# Pulse_Oximeter_Board.net
KiCad netlist of a schematic drawn in EAGLE
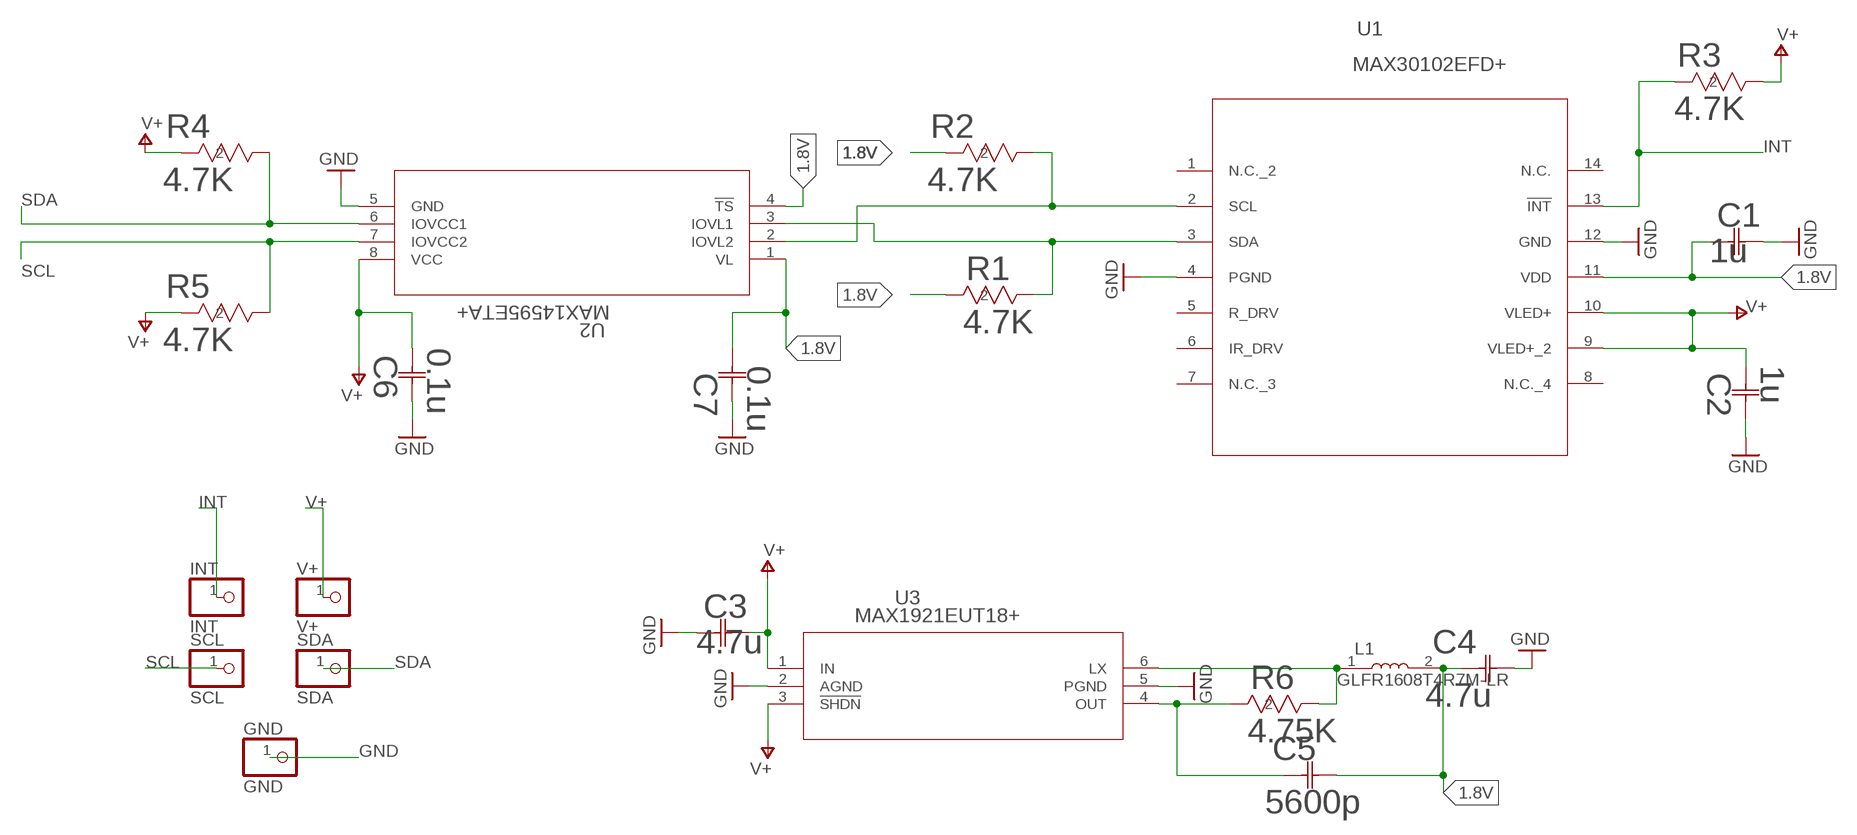
[diagram p0: schematic, sheet 1]

(export (version "E")
  (design (tool "Eeschema 10.0.6"))
  (components
    (comp (ref "C1")
      (value "1u")
      (footprint "eagle-import:CAP_CHIP2_1X0P5")
      (fields (field (name "MANUFACTURER_PART_NUMBER") "GRM155R61A105KE15D"))
      (libsource (lib "eagle-import") (part "GRM155R61A105KE15D"))
    )
    (comp (ref "C2")
      (value "1u")
      (footprint "eagle-import:CAP_CHIP2_1X0P5")
      (fields (field (name "MANUFACTURER_PART_NUMBER") "GRM155R61A105KE15D"))
      (libsource (lib "eagle-import") (part "GRM155R61A105KE15D"))
    )
    (comp (ref "C3")
      (value "4.7u")
      (footprint "eagle-import:CAP_CHIP2_1X0P5")
      (fields (field (name "MANUFACTURER_PART_NUMBER") "GRM155R61A105KE15D"))
      (libsource (lib "eagle-import") (part "GRM155R61A105KE15D"))
    )
    (comp (ref "C4")
      (value "4.7u")
      (footprint "eagle-import:CAP_CHIP2_1X0P5")
      (fields (field (name "MANUFACTURER_PART_NUMBER") "GRM155R61A105KE15D"))
      (libsource (lib "eagle-import") (part "GRM155R61A105KE15D"))
    )
    (comp (ref "C5")
      (value "5600p")
      (footprint "eagle-import:CAP_CHIP2_1X0P5")
      (fields (field (name "MANUFACTURER_PART_NUMBER") "GRM155R61A105KE15D"))
      (libsource (lib "eagle-import") (part "GRM155R61A105KE15D"))
    )
    (comp (ref "C6")
      (value "0.1u")
      (footprint "eagle-import:CAP_CHIP2_1X0P5")
      (fields (field (name "MANUFACTURER_PART_NUMBER") "GRM155R61A105KE15D"))
      (libsource (lib "eagle-import") (part "GRM155R61A105KE15D"))
    )
    (comp (ref "C7")
      (value "0.1u")
      (footprint "eagle-import:CAP_CHIP2_1X0P5")
      (fields (field (name "MANUFACTURER_PART_NUMBER") "GRM155R61A105KE15D"))
      (libsource (lib "eagle-import") (part "GRM155R61A105KE15D"))
    )
    (comp (ref "GND")
      (value "GND")
      (footprint "eagle-import:1X01")
      (libsource (lib "eagle-import") (part "PINHD-1X1"))
    )
    (comp (ref "INT")
      (value "INT")
      (footprint "eagle-import:1X01")
      (libsource (lib "eagle-import") (part "PINHD-1X1"))
    )
    (comp (ref "L1")
      (value "GLFR1608T4R7M-LR")
      (footprint "eagle-import:INDC1608X95N")
      (fields (field (name "DIGI-KEY_PART_NUMBER") "445-3607-1-ND") (field (name "MF") "TDK"))
      (libsource (lib "eagle-import") (part "GLFR1608T4R7M-LR"))
    )
    (comp (ref "R1")
      (value "4.7K")
      (footprint "eagle-import:RES0402_CRG_TYCO")
      (fields (field (name "MANUFACTURER_PART_NUMBER") "CRG0402J1K010"))
      (libsource (lib "eagle-import") (part "CRG0402J1K0/10"))
    )
    (comp (ref "R2")
      (value "4.7K")
      (footprint "eagle-import:RES0402_CRG_TYCO")
      (fields (field (name "MANUFACTURER_PART_NUMBER") "CRG0402J1K010"))
      (libsource (lib "eagle-import") (part "CRG0402J1K0/10"))
    )
    (comp (ref "R3")
      (value "4.7K")
      (footprint "eagle-import:RES0402_CRG_TYCO")
      (fields (field (name "MANUFACTURER_PART_NUMBER") "CRG0402J1K010"))
      (libsource (lib "eagle-import") (part "CRG0402J1K0/10"))
    )
    (comp (ref "R4")
      (value "4.7K")
      (footprint "eagle-import:RES0402_CRG_TYCO")
      (fields (field (name "MANUFACTURER_PART_NUMBER") "CRG0402J1K010"))
      (libsource (lib "eagle-import") (part "CRG0402J1K0/10"))
    )
    (comp (ref "R5")
      (value "4.7K")
      (footprint "eagle-import:RES0402_CRG_TYCO")
      (fields (field (name "MANUFACTURER_PART_NUMBER") "CRG0402J1K010"))
      (libsource (lib "eagle-import") (part "CRG0402J1K0/10"))
    )
    (comp (ref "R6")
      (value "4.75K")
      (footprint "eagle-import:RES0402_CRG_TYCO")
      (fields (field (name "MANUFACTURER_PART_NUMBER") "CRG0402J1K010"))
      (libsource (lib "eagle-import") (part "CRG0402J1K0/10"))
    )
    (comp (ref "SCL")
      (value "SCL")
      (footprint "eagle-import:1X01")
      (libsource (lib "eagle-import") (part "PINHD-1X1"))
    )
    (comp (ref "SDA")
      (value "SDA")
      (footprint "eagle-import:1X01")
      (libsource (lib "eagle-import") (part "PINHD-1X1"))
    )
    (comp (ref "U1")
      (value "MAX30102EFD+")
      (footprint "eagle-import:21-0880B")
      (libsource (lib "eagle-import") (part "MAX30102EFD+"))
    )
    (comp (ref "U2")
      (value "MAX14595ETA+")
      (footprint "eagle-import:21-0487A")
      (libsource (lib "eagle-import") (part "MAX14595ETA+"))
    )
    (comp (ref "U3")
      (value "MAX1921EUT18+")
      (footprint "eagle-import:21-0058I")
      (libsource (lib "eagle-import") (part "MAX1921EUT18+"))
    )
    (comp (ref "V+")
      (value "V+")
      (footprint "eagle-import:1X01")
      (libsource (lib "eagle-import") (part "PINHD-1X1"))
    )
  )
  (nets
    (net (code "1") (name "/INT") (class "Default")
      (node (ref "INT") (pin "1") (pinfunction "1_1") (pintype "passive"))
      (node (ref "R3") (pin "2") (pinfunction "2_2") (pintype "passive"))
      (node (ref "U1") (pin "13") (pinfunction "~{INT}_13") (pintype "passive"))
    )
    (net (code "2") (name "/SCL") (class "Default")
      (node (ref "R5") (pin "1") (pinfunction "1_1") (pintype "passive"))
      (node (ref "SCL") (pin "1") (pinfunction "1_1") (pintype "passive"))
      (node (ref "U2") (pin "7") (pinfunction "IOVCC2_7") (pintype "passive"))
    )
    (net (code "3") (name "/SDA") (class "Default")
      (node (ref "R4") (pin "1") (pinfunction "1_1") (pintype "passive"))
      (node (ref "SDA") (pin "1") (pinfunction "1_1") (pintype "passive"))
      (node (ref "U2") (pin "6") (pinfunction "IOVCC1_6") (pintype "passive"))
    )
    (net (code "4") (name "1.8V") (class "Default")
      (node (ref "C1") (pin "1") (pinfunction "1_1") (pintype "passive"))
      (node (ref "C4") (pin "1") (pinfunction "1_1") (pintype "passive"))
      (node (ref "C5") (pin "2") (pinfunction "2_2") (pintype "passive"))
      (node (ref "C7") (pin "1") (pinfunction "1_1") (pintype "passive"))
      (node (ref "L1") (pin "2") (pinfunction "2_2") (pintype "passive"))
      (node (ref "R1") (pin "2") (pinfunction "2_2") (pintype "passive"))
      (node (ref "R2") (pin "2") (pinfunction "2_2") (pintype "passive"))
      (node (ref "U1") (pin "11") (pinfunction "VDD_11") (pintype "power_in"))
      (node (ref "U2") (pin "1") (pinfunction "VL_1") (pintype "power_in"))
      (node (ref "U2") (pin "4") (pinfunction "~{TS}_4") (pintype "passive"))
    )
    (net (code "5") (name "GND") (class "Default")
      (node (ref "C1") (pin "2") (pinfunction "2_2") (pintype "passive"))
      (node (ref "C2") (pin "2") (pinfunction "2_2") (pintype "passive"))
      (node (ref "C3") (pin "1") (pinfunction "1_1") (pintype "passive"))
      (node (ref "C4") (pin "2") (pinfunction "2_2") (pintype "passive"))
      (node (ref "C6") (pin "2") (pinfunction "2_2") (pintype "passive"))
      (node (ref "C7") (pin "2") (pinfunction "2_2") (pintype "passive"))
      (node (ref "GND") (pin "1") (pinfunction "1_1") (pintype "passive"))
      (node (ref "U1") (pin "12") (pinfunction "GND_12") (pintype "power_in"))
      (node (ref "U1") (pin "4") (pinfunction "PGND_4") (pintype "power_in"))
      (node (ref "U2") (pin "5") (pinfunction "GND_5") (pintype "power_in"))
      (node (ref "U3") (pin "2") (pinfunction "AGND_2") (pintype "power_in"))
      (node (ref "U3") (pin "5") (pinfunction "PGND_5") (pintype "power_in"))
    )
    (net (code "6") (name "Net-(U1-SCL)") (class "Default")
      (node (ref "R2") (pin "1") (pinfunction "1_1") (pintype "passive"))
      (node (ref "U1") (pin "2") (pinfunction "SCL_2") (pintype "input"))
      (node (ref "U2") (pin "2") (pinfunction "IOVL2_2") (pintype "passive"))
    )
    (net (code "7") (name "Net-(U1-SDA)") (class "Default")
      (node (ref "R1") (pin "1") (pinfunction "1_1") (pintype "passive"))
      (node (ref "U1") (pin "3") (pinfunction "SDA_3") (pintype "bidirectional"))
      (node (ref "U2") (pin "3") (pinfunction "IOVL1_3") (pintype "passive"))
    )
    (net (code "8") (name "Net-(U3-LX)") (class "Default")
      (node (ref "L1") (pin "1") (pinfunction "1_1") (pintype "passive"))
      (node (ref "R6") (pin "1") (pinfunction "1_1") (pintype "passive"))
      (node (ref "U3") (pin "6") (pinfunction "LX_6") (pintype "passive"))
    )
    (net (code "9") (name "Net-(U3-OUT)") (class "Default")
      (node (ref "C5") (pin "1") (pinfunction "1_1") (pintype "passive"))
      (node (ref "R6") (pin "2") (pinfunction "2_2") (pintype "passive"))
      (node (ref "U3") (pin "4") (pinfunction "OUT_4") (pintype "output"))
    )
    (net (code "10") (name "V+") (class "Default")
      (node (ref "C2") (pin "1") (pinfunction "1_1") (pintype "passive"))
      (node (ref "C3") (pin "2") (pinfunction "2_2") (pintype "passive"))
      (node (ref "C6") (pin "1") (pinfunction "1_1") (pintype "passive"))
      (node (ref "R3") (pin "1") (pinfunction "1_1") (pintype "passive"))
      (node (ref "R4") (pin "2") (pinfunction "2_2") (pintype "passive"))
      (node (ref "R5") (pin "2") (pinfunction "2_2") (pintype "passive"))
      (node (ref "U1") (pin "10") (pinfunction "VLED+_10") (pintype "passive"))
      (node (ref "U1") (pin "9") (pinfunction "VLED+_2_9") (pintype "passive"))
      (node (ref "U2") (pin "8") (pinfunction "VCC_8") (pintype "power_in"))
      (node (ref "U3") (pin "1") (pinfunction "IN_1") (pintype "input"))
      (node (ref "U3") (pin "3") (pinfunction "~{SHDN}_3") (pintype "passive"))
      (node (ref "V+") (pin "1") (pinfunction "1_1") (pintype "passive"))
    )
    (net (code "11") (name "unconnected-(U1-IR_DRV-Pad6)") (class "Default")
      (node (ref "U1") (pin "6") (pinfunction "IR_DRV_6") (pintype "passive"))
    )
    (net (code "12") (name "unconnected-(U1-N.C.-Pad14)") (class "Default")
      (node (ref "U1") (pin "14") (pinfunction "N.C._14") (pintype "no_connect"))
    )
    (net (code "13") (name "unconnected-(U1-N.C._2-Pad1)") (class "Default")
      (node (ref "U1") (pin "1") (pinfunction "N.C._2_1") (pintype "no_connect"))
    )
    (net (code "14") (name "unconnected-(U1-N.C._3-Pad7)") (class "Default")
      (node (ref "U1") (pin "7") (pinfunction "N.C._3_7") (pintype "no_connect"))
    )
    (net (code "15") (name "unconnected-(U1-N.C._4-Pad8)") (class "Default")
      (node (ref "U1") (pin "8") (pinfunction "N.C._4_8") (pintype "no_connect"))
    )
    (net (code "16") (name "unconnected-(U1-R_DRV-Pad5)") (class "Default")
      (node (ref "U1") (pin "5") (pinfunction "R_DRV_5") (pintype "passive"))
    )
  )
)
